# receiver_rfm95.net
KiCad netlist of a schematic drawn in EAGLE
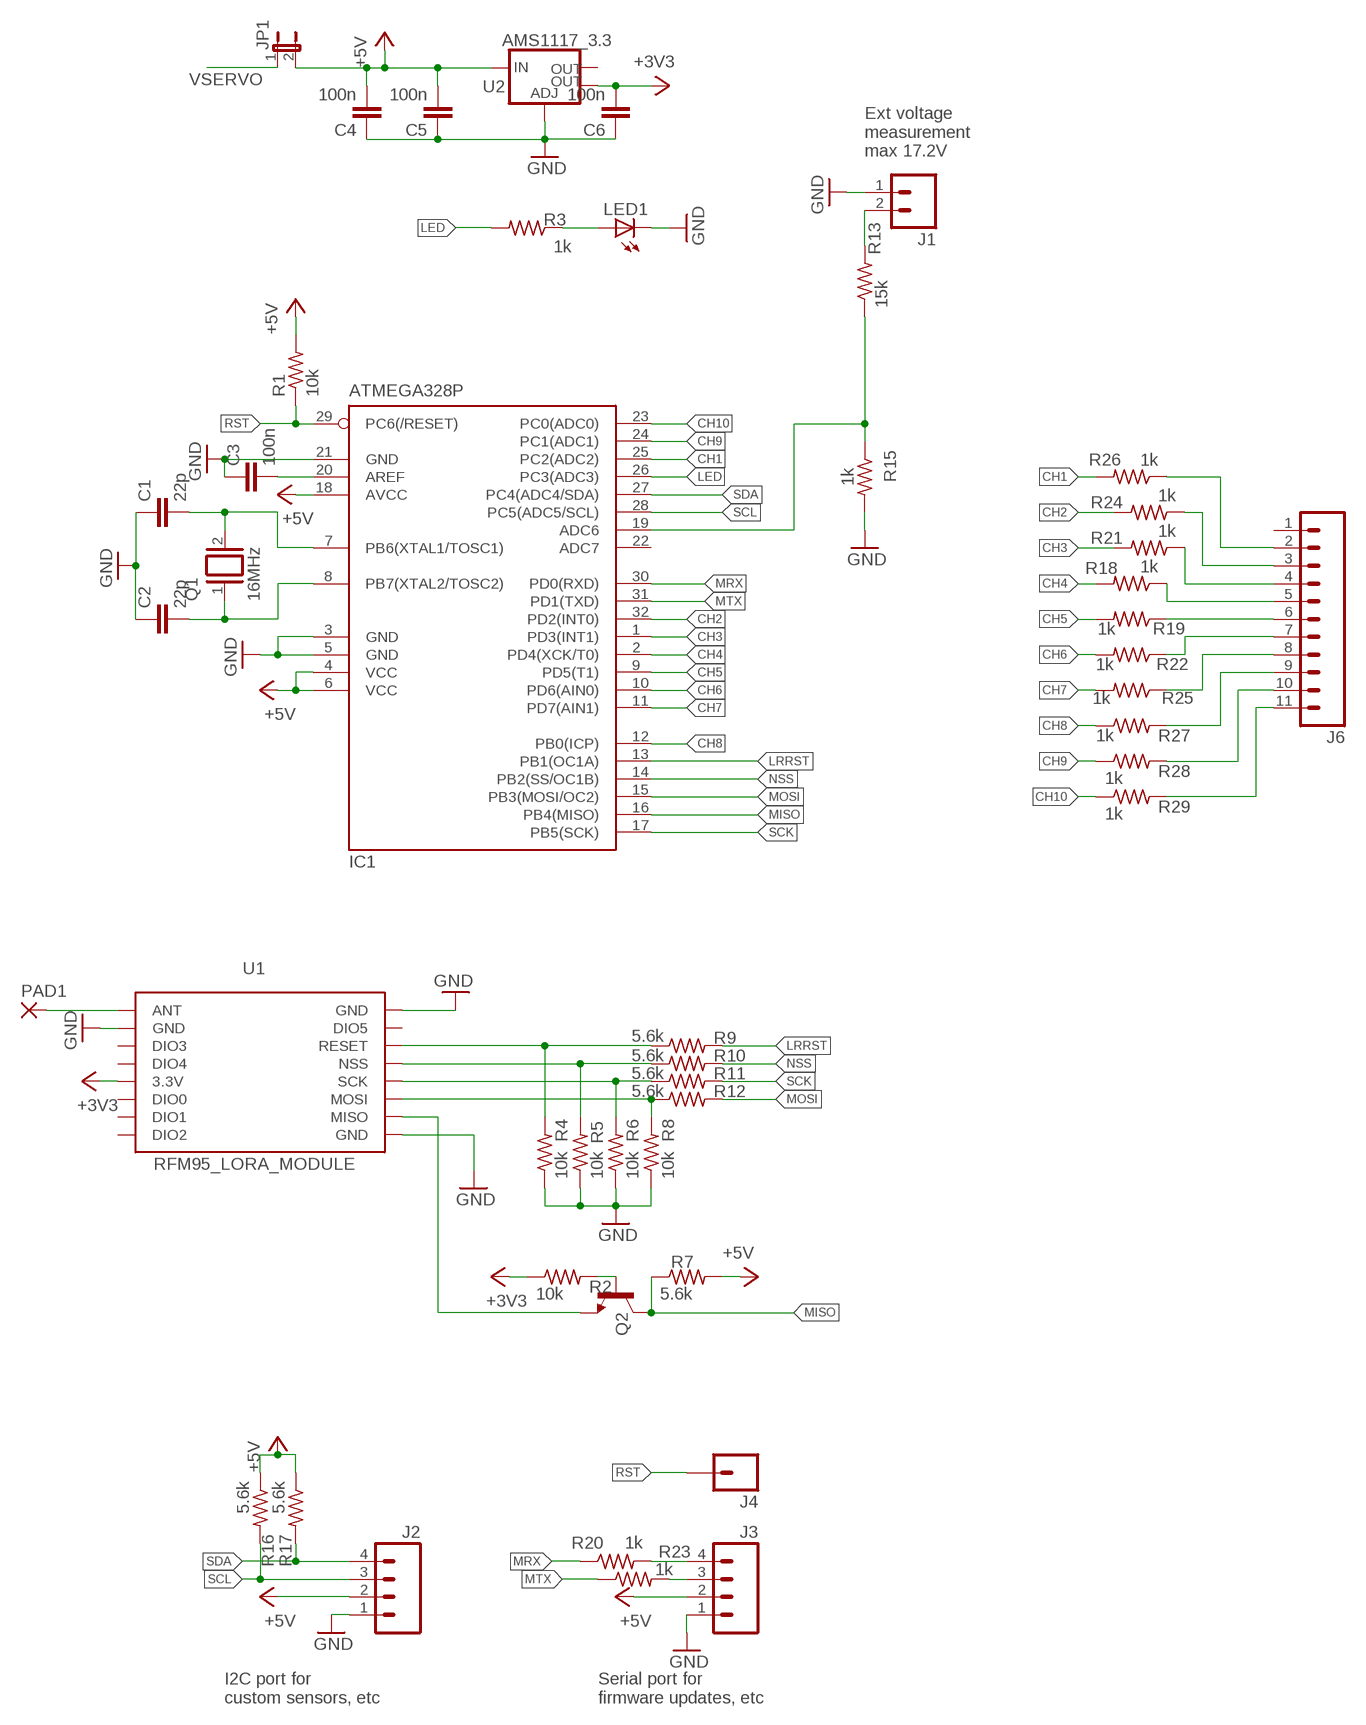
[diagram p0: schematic, sheet 1]

(export (version "E")
  (design (tool "Eeschema 10.0.6"))
  (components
    (comp (ref "C1")
      (value "22p")
      (footprint "eagle-import:C0805K")
      (libsource (lib "eagle-import") (part "C-EUC0805K"))
    )
    (comp (ref "C2")
      (value "22p")
      (footprint "eagle-import:C0805K")
      (libsource (lib "eagle-import") (part "C-EUC0805K"))
    )
    (comp (ref "C3")
      (value "100n")
      (footprint "eagle-import:C0805K")
      (libsource (lib "eagle-import") (part "C-EUC0805K"))
    )
    (comp (ref "C4")
      (value "100n")
      (footprint "eagle-import:C0805K")
      (libsource (lib "eagle-import") (part "C-EUC0805K"))
    )
    (comp (ref "C5")
      (value "100n")
      (footprint "eagle-import:C0805K")
      (libsource (lib "eagle-import") (part "C-EUC0805K"))
    )
    (comp (ref "C6")
      (value "100n")
      (footprint "eagle-import:C0805K")
      (libsource (lib "eagle-import") (part "C-EUC0805K"))
    )
    (comp (ref "IC1")
      (value "ATMEGA328P")
      (footprint "eagle-import:TQFP32-08")
      (fields (field (name "MPN") "ATMEGA8-16AU"))
      (libsource (lib "eagle-import") (part "MEGA8-AI"))
    )
    (comp (ref "J1")
      (value "M02PTH")
      (footprint "eagle-import:1X02")
      (libsource (lib "eagle-import") (part "M02PTH"))
    )
    (comp (ref "J2")
      (value "M04PTH")
      (footprint "eagle-import:1X04")
      (libsource (lib "eagle-import") (part "M04PTH"))
    )
    (comp (ref "J3")
      (value "M04PTH")
      (footprint "eagle-import:1X04")
      (libsource (lib "eagle-import") (part "M04PTH"))
    )
    (comp (ref "J4")
      (value "M01PTH")
      (footprint "eagle-import:1X01")
      (libsource (lib "eagle-import") (part "M01PTH"))
    )
    (comp (ref "J6")
      (value "M11PTH")
      (footprint "eagle-import:1X11")
      (libsource (lib "eagle-import") (part "M11PTH"))
    )
    (comp (ref "JP1")
      (value "JP1E")
      (footprint "eagle-import:JP1")
      (libsource (lib "eagle-import") (part "JP1E"))
    )
    (comp (ref "LED1")
      (value "LEDCHIPLED_1206")
      (footprint "eagle-import:CHIPLED_1206")
      (libsource (lib "eagle-import") (part "LEDCHIPLED_1206"))
    )
    (comp (ref "PAD1")
      (value "2,15/1,0")
      (footprint "eagle-import:2,15_1,0")
      (libsource (lib "eagle-import") (part "2,15/1,0"))
    )
    (comp (ref "Q1")
      (value "16MHz")
      (footprint "eagle-import:QS")
      (libsource (lib "eagle-import") (part "XTAL/S"))
    )
    (comp (ref "Q2")
      (value "BC817-16SMD")
      (footprint "eagle-import:SOT23-BEC")
      (libsource (lib "eagle-import") (part "BC817SMD-16"))
    )
    (comp (ref "R1")
      (value "10k")
      (footprint "eagle-import:R0805")
      (libsource (lib "eagle-import") (part "R-US_R0805"))
    )
    (comp (ref "R2")
      (value "10k")
      (footprint "eagle-import:R0805")
      (libsource (lib "eagle-import") (part "R-US_R0805"))
    )
    (comp (ref "R3")
      (value "1k")
      (footprint "eagle-import:R0805")
      (libsource (lib "eagle-import") (part "R-US_R0805"))
    )
    (comp (ref "R4")
      (value "10k")
      (footprint "eagle-import:R0805")
      (libsource (lib "eagle-import") (part "R-US_R0805"))
    )
    (comp (ref "R5")
      (value "10k")
      (footprint "eagle-import:R0805")
      (libsource (lib "eagle-import") (part "R-US_R0805"))
    )
    (comp (ref "R6")
      (value "10k")
      (footprint "eagle-import:R0805")
      (libsource (lib "eagle-import") (part "R-US_R0805"))
    )
    (comp (ref "R7")
      (value "5.6k")
      (footprint "eagle-import:R0805")
      (libsource (lib "eagle-import") (part "R-US_R0805"))
    )
    (comp (ref "R8")
      (value "10k")
      (footprint "eagle-import:R0805")
      (libsource (lib "eagle-import") (part "R-US_R0805"))
    )
    (comp (ref "R9")
      (value "5.6k")
      (footprint "eagle-import:R0805")
      (libsource (lib "eagle-import") (part "R-US_R0805"))
    )
    (comp (ref "R10")
      (value "5.6k")
      (footprint "eagle-import:R0805")
      (libsource (lib "eagle-import") (part "R-US_R0805"))
    )
    (comp (ref "R11")
      (value "5.6k")
      (footprint "eagle-import:R0805")
      (libsource (lib "eagle-import") (part "R-US_R0805"))
    )
    (comp (ref "R12")
      (value "5.6k")
      (footprint "eagle-import:R0805")
      (libsource (lib "eagle-import") (part "R-US_R0805"))
    )
    (comp (ref "R13")
      (value "15k")
      (footprint "eagle-import:R0805")
      (libsource (lib "eagle-import") (part "R-US_R0805"))
    )
    (comp (ref "R15")
      (value "1k")
      (footprint "eagle-import:R0805")
      (libsource (lib "eagle-import") (part "R-US_R0805"))
    )
    (comp (ref "R16")
      (value "5.6k")
      (footprint "eagle-import:R0805")
      (libsource (lib "eagle-import") (part "R-US_R0805"))
    )
    (comp (ref "R17")
      (value "5.6k")
      (footprint "eagle-import:R0805")
      (libsource (lib "eagle-import") (part "R-US_R0805"))
    )
    (comp (ref "R18")
      (value "1k")
      (footprint "eagle-import:R0805")
      (libsource (lib "eagle-import") (part "R-US_R0805"))
    )
    (comp (ref "R19")
      (value "1k")
      (footprint "eagle-import:R0805")
      (libsource (lib "eagle-import") (part "R-US_R0805"))
    )
    (comp (ref "R20")
      (value "1k")
      (footprint "eagle-import:R0805")
      (libsource (lib "eagle-import") (part "R-US_R0805"))
    )
    (comp (ref "R21")
      (value "1k")
      (footprint "eagle-import:R0805")
      (libsource (lib "eagle-import") (part "R-US_R0805"))
    )
    (comp (ref "R22")
      (value "1k")
      (footprint "eagle-import:R0805")
      (libsource (lib "eagle-import") (part "R-US_R0805"))
    )
    (comp (ref "R23")
      (value "1k")
      (footprint "eagle-import:R0805")
      (libsource (lib "eagle-import") (part "R-US_R0805"))
    )
    (comp (ref "R24")
      (value "1k")
      (footprint "eagle-import:R0805")
      (libsource (lib "eagle-import") (part "R-US_R0805"))
    )
    (comp (ref "R25")
      (value "1k")
      (footprint "eagle-import:R0805")
      (libsource (lib "eagle-import") (part "R-US_R0805"))
    )
    (comp (ref "R26")
      (value "1k")
      (footprint "eagle-import:R0805")
      (libsource (lib "eagle-import") (part "R-US_R0805"))
    )
    (comp (ref "R27")
      (value "1k")
      (footprint "eagle-import:R0805")
      (libsource (lib "eagle-import") (part "R-US_R0805"))
    )
    (comp (ref "R28")
      (value "1k")
      (footprint "eagle-import:R0805")
      (libsource (lib "eagle-import") (part "R-US_R0805"))
    )
    (comp (ref "R29")
      (value "1k")
      (footprint "eagle-import:R0805")
      (libsource (lib "eagle-import") (part "R-US_R0805"))
    )
    (comp (ref "U1")
      (value "RFM95_LORA_MODULE")
      (footprint "eagle-import:RFM95")
      (libsource (lib "eagle-import") (part "RFM95_LORA_MODULE"))
    )
    (comp (ref "U2")
      (value "AMS1117_3.3")
      (footprint "eagle-import:SOT223")
      (libsource (lib "eagle-import") (part "V_REG_LM1117SOT223"))
    )
  )
  (nets
    (net (code "1") (name "+3V3") (class "Default")
      (node (ref "C6") (pin "2") (pinfunction "2_2") (pintype "passive"))
      (node (ref "R2") (pin "1") (pinfunction "1_1") (pintype "passive"))
      (node (ref "U1") (pin "3.3V") (pinfunction "3.3V_3.3V") (pintype "bidirectional"))
      (node (ref "U2") (pin "4") (pinfunction "OUT_4") (pintype "output"))
    )
    (net (code "2") (name "+5V") (class "Default")
      (node (ref "C4") (pin "2") (pinfunction "2_2") (pintype "passive"))
      (node (ref "C5") (pin "2") (pinfunction "2_2") (pintype "passive"))
      (node (ref "IC1") (pin "18") (pinfunction "AVCC_18") (pintype "power_in"))
      (node (ref "IC1") (pin "4") (pinfunction "VCC_4") (pintype "power_in"))
      (node (ref "IC1") (pin "6") (pinfunction "VCC_6") (pintype "power_in"))
      (node (ref "J2") (pin "2") (pinfunction "2_2") (pintype "passive"))
      (node (ref "J3") (pin "2") (pinfunction "2_2") (pintype "passive"))
      (node (ref "JP1") (pin "2") (pinfunction "2_2") (pintype "passive"))
      (node (ref "R1") (pin "2") (pinfunction "2_2") (pintype "passive"))
      (node (ref "R16") (pin "1") (pinfunction "1_1") (pintype "passive"))
      (node (ref "R17") (pin "1") (pinfunction "1_1") (pintype "passive"))
      (node (ref "R7") (pin "2") (pinfunction "2_2") (pintype "passive"))
      (node (ref "U2") (pin "3") (pinfunction "IN_3") (pintype "input"))
    )
    (net (code "3") (name "/DIO3") (class "Default")
      (node (ref "U1") (pin "DIO3") (pinfunction "DIO3_DIO3") (pintype "power_in"))
    )
    (net (code "4") (name "/VSERVO") (class "Default")
      (node (ref "JP1") (pin "1") (pinfunction "1_1") (pintype "passive"))
    )
    (net (code "5") (name "CH1") (class "Default")
      (node (ref "IC1") (pin "25") (pinfunction "PC2(ADC2)_25") (pintype "bidirectional"))
      (node (ref "R26") (pin "2") (pinfunction "2_2") (pintype "passive"))
    )
    (net (code "6") (name "CH2") (class "Default")
      (node (ref "IC1") (pin "32") (pinfunction "PD2(INT0)_32") (pintype "bidirectional"))
      (node (ref "R24") (pin "2") (pinfunction "2_2") (pintype "passive"))
    )
    (net (code "7") (name "CH3") (class "Default")
      (node (ref "IC1") (pin "1") (pinfunction "PD3(INT1)_1") (pintype "bidirectional"))
      (node (ref "R21") (pin "2") (pinfunction "2_2") (pintype "passive"))
    )
    (net (code "8") (name "CH4") (class "Default")
      (node (ref "IC1") (pin "2") (pinfunction "PD4(XCK/T0)_2") (pintype "bidirectional"))
      (node (ref "R18") (pin "2") (pinfunction "2_2") (pintype "passive"))
    )
    (net (code "9") (name "CH5") (class "Default")
      (node (ref "IC1") (pin "9") (pinfunction "PD5(T1)_9") (pintype "bidirectional"))
      (node (ref "R19") (pin "2") (pinfunction "2_2") (pintype "passive"))
    )
    (net (code "10") (name "CH6") (class "Default")
      (node (ref "IC1") (pin "10") (pinfunction "PD6(AIN0)_10") (pintype "bidirectional"))
      (node (ref "R22") (pin "2") (pinfunction "2_2") (pintype "passive"))
    )
    (net (code "11") (name "CH7") (class "Default")
      (node (ref "IC1") (pin "11") (pinfunction "PD7(AIN1)_11") (pintype "bidirectional"))
      (node (ref "R25") (pin "2") (pinfunction "2_2") (pintype "passive"))
    )
    (net (code "12") (name "CH8") (class "Default")
      (node (ref "IC1") (pin "12") (pinfunction "PB0(ICP)_12") (pintype "bidirectional"))
      (node (ref "R27") (pin "1") (pinfunction "1_1") (pintype "passive"))
    )
    (net (code "13") (name "CH9") (class "Default")
      (node (ref "IC1") (pin "24") (pinfunction "PC1(ADC1)_24") (pintype "bidirectional"))
      (node (ref "R28") (pin "1") (pinfunction "1_1") (pintype "passive"))
    )
    (net (code "14") (name "CH10") (class "Default")
      (node (ref "IC1") (pin "23") (pinfunction "PC0(ADC0)_23") (pintype "bidirectional"))
      (node (ref "R29") (pin "1") (pinfunction "1_1") (pintype "passive"))
    )
    (net (code "15") (name "GND") (class "Default")
      (node (ref "C1") (pin "1") (pinfunction "1_1") (pintype "passive"))
      (node (ref "C2") (pin "1") (pinfunction "1_1") (pintype "passive"))
      (node (ref "C3") (pin "1") (pinfunction "1_1") (pintype "passive"))
      (node (ref "C4") (pin "1") (pinfunction "1_1") (pintype "passive"))
      (node (ref "C5") (pin "1") (pinfunction "1_1") (pintype "passive"))
      (node (ref "C6") (pin "1") (pinfunction "1_1") (pintype "passive"))
      (node (ref "IC1") (pin "21") (pinfunction "GND_21") (pintype "power_in"))
      (node (ref "IC1") (pin "3") (pinfunction "GND_3") (pintype "power_in"))
      (node (ref "IC1") (pin "5") (pinfunction "GND_5") (pintype "power_in"))
      (node (ref "J1") (pin "1") (pinfunction "1_1") (pintype "passive"))
      (node (ref "J2") (pin "1") (pinfunction "1_1") (pintype "passive"))
      (node (ref "J3") (pin "1") (pinfunction "1_1") (pintype "passive"))
      (node (ref "LED1") (pin "C") (pinfunction "C_C") (pintype "passive"))
      (node (ref "R15") (pin "2") (pinfunction "2_2") (pintype "passive"))
      (node (ref "R4") (pin "1") (pinfunction "1_1") (pintype "passive"))
      (node (ref "R5") (pin "1") (pinfunction "1_1") (pintype "passive"))
      (node (ref "R6") (pin "1") (pinfunction "1_1") (pintype "passive"))
      (node (ref "R8") (pin "1") (pinfunction "1_1") (pintype "passive"))
      (node (ref "U1") (pin "GND") (pinfunction "GND_GND") (pintype "power_in"))
      (node (ref "U1") (pin "GND@1") (pinfunction "GND_GND@1") (pintype "power_in"))
      (node (ref "U1") (pin "GND@2") (pinfunction "GND_GND@2") (pintype "power_in"))
      (node (ref "U2") (pin "1") (pinfunction "ADJ_1") (pintype "input"))
    )
    (net (code "16") (name "LED") (class "Default")
      (node (ref "IC1") (pin "26") (pinfunction "PC3(ADC3)_26") (pintype "bidirectional"))
      (node (ref "R3") (pin "2") (pinfunction "2_2") (pintype "passive"))
    )
    (net (code "17") (name "LRRST") (class "Default")
      (node (ref "IC1") (pin "13") (pinfunction "PB1(OC1A)_13") (pintype "bidirectional"))
      (node (ref "R9") (pin "2") (pinfunction "2_2") (pintype "passive"))
    )
    (net (code "18") (name "MISO") (class "Default")
      (node (ref "IC1") (pin "16") (pinfunction "PB4(MISO)_16") (pintype "bidirectional"))
      (node (ref "Q2") (pin "C") (pinfunction "C_C") (pintype "passive"))
      (node (ref "R7") (pin "1") (pinfunction "1_1") (pintype "passive"))
    )
    (net (code "19") (name "MOSI") (class "Default")
      (node (ref "IC1") (pin "15") (pinfunction "PB3(MOSI/OC2)_15") (pintype "bidirectional"))
      (node (ref "R12") (pin "2") (pinfunction "2_2") (pintype "passive"))
    )
    (net (code "20") (name "MRX") (class "Default")
      (node (ref "IC1") (pin "30") (pinfunction "PD0(RXD)_30") (pintype "bidirectional"))
      (node (ref "R20") (pin "1") (pinfunction "1_1") (pintype "passive"))
    )
    (net (code "21") (name "MTX") (class "Default")
      (node (ref "IC1") (pin "31") (pinfunction "PD1(TXD)_31") (pintype "bidirectional"))
      (node (ref "R23") (pin "1") (pinfunction "1_1") (pintype "passive"))
    )
    (net (code "22") (name "NSS") (class "Default")
      (node (ref "IC1") (pin "14") (pinfunction "PB2(SS/OC1B)_14") (pintype "bidirectional"))
      (node (ref "R10") (pin "2") (pinfunction "2_2") (pintype "passive"))
    )
    (net (code "23") (name "Net-(IC1-ADC6)") (class "Default")
      (node (ref "IC1") (pin "19") (pinfunction "ADC6_19") (pintype "bidirectional"))
      (node (ref "R13") (pin "1") (pinfunction "1_1") (pintype "passive"))
      (node (ref "R15") (pin "1") (pinfunction "1_1") (pintype "passive"))
    )
    (net (code "24") (name "Net-(IC1-AREF)") (class "Default")
      (node (ref "C3") (pin "2") (pinfunction "2_2") (pintype "passive"))
      (node (ref "IC1") (pin "20") (pinfunction "AREF_20") (pintype "passive"))
    )
    (net (code "25") (name "Net-(IC1-PB6(XTAL1{slash}TOSC1))") (class "Default")
      (node (ref "C1") (pin "2") (pinfunction "2_2") (pintype "passive"))
      (node (ref "IC1") (pin "7") (pinfunction "PB6(XTAL1/TOSC1)_7") (pintype "bidirectional"))
      (node (ref "Q1") (pin "2") (pinfunction "2_2") (pintype "passive"))
    )
    (net (code "26") (name "Net-(IC1-PB7(XTAL2{slash}TOSC2))") (class "Default")
      (node (ref "C2") (pin "2") (pinfunction "2_2") (pintype "passive"))
      (node (ref "IC1") (pin "8") (pinfunction "PB7(XTAL2/TOSC2)_8") (pintype "bidirectional"))
      (node (ref "Q1") (pin "1") (pinfunction "1_1") (pintype "passive"))
    )
    (net (code "27") (name "Net-(J1-Pad2)") (class "Default")
      (node (ref "J1") (pin "2") (pinfunction "2_2") (pintype "passive"))
      (node (ref "R13") (pin "2") (pinfunction "2_2") (pintype "passive"))
    )
    (net (code "28") (name "Net-(J3-Pad3)") (class "Default")
      (node (ref "J3") (pin "3") (pinfunction "3_3") (pintype "passive"))
      (node (ref "R23") (pin "2") (pinfunction "2_2") (pintype "passive"))
    )
    (net (code "29") (name "Net-(J3-Pad4)") (class "Default")
      (node (ref "J3") (pin "4") (pinfunction "4_4") (pintype "passive"))
      (node (ref "R20") (pin "2") (pinfunction "2_2") (pintype "passive"))
    )
    (net (code "30") (name "Net-(J6-Pad2)") (class "Default")
      (node (ref "J6") (pin "2") (pinfunction "2_2") (pintype "passive"))
      (node (ref "R26") (pin "1") (pinfunction "1_1") (pintype "passive"))
    )
    (net (code "31") (name "Net-(J6-Pad3)") (class "Default")
      (node (ref "J6") (pin "3") (pinfunction "3_3") (pintype "passive"))
      (node (ref "R24") (pin "1") (pinfunction "1_1") (pintype "passive"))
    )
    (net (code "32") (name "Net-(J6-Pad4)") (class "Default")
      (node (ref "J6") (pin "4") (pinfunction "4_4") (pintype "passive"))
      (node (ref "R21") (pin "1") (pinfunction "1_1") (pintype "passive"))
    )
    (net (code "33") (name "Net-(J6-Pad5)") (class "Default")
      (node (ref "J6") (pin "5") (pinfunction "5_5") (pintype "passive"))
      (node (ref "R18") (pin "1") (pinfunction "1_1") (pintype "passive"))
    )
    (net (code "34") (name "Net-(J6-Pad6)") (class "Default")
      (node (ref "J6") (pin "6") (pinfunction "6_6") (pintype "passive"))
      (node (ref "R19") (pin "1") (pinfunction "1_1") (pintype "passive"))
    )
    (net (code "35") (name "Net-(J6-Pad7)") (class "Default")
      (node (ref "J6") (pin "7") (pinfunction "7_7") (pintype "passive"))
      (node (ref "R22") (pin "1") (pinfunction "1_1") (pintype "passive"))
    )
    (net (code "36") (name "Net-(J6-Pad8)") (class "Default")
      (node (ref "J6") (pin "8") (pinfunction "8_8") (pintype "passive"))
      (node (ref "R25") (pin "1") (pinfunction "1_1") (pintype "passive"))
    )
    (net (code "37") (name "Net-(J6-Pad9)") (class "Default")
      (node (ref "J6") (pin "9") (pinfunction "9_9") (pintype "passive"))
      (node (ref "R27") (pin "2") (pinfunction "2_2") (pintype "passive"))
    )
    (net (code "38") (name "Net-(J6-Pad10)") (class "Default")
      (node (ref "J6") (pin "10") (pinfunction "10_10") (pintype "passive"))
      (node (ref "R28") (pin "2") (pinfunction "2_2") (pintype "passive"))
    )
    (net (code "39") (name "Net-(J6-Pad11)") (class "Default")
      (node (ref "J6") (pin "11") (pinfunction "11_11") (pintype "passive"))
      (node (ref "R29") (pin "2") (pinfunction "2_2") (pintype "passive"))
    )
    (net (code "40") (name "Net-(LED1-PadA)") (class "Default")
      (node (ref "LED1") (pin "A") (pinfunction "A_A") (pintype "passive"))
      (node (ref "R3") (pin "1") (pinfunction "1_1") (pintype "passive"))
    )
    (net (code "41") (name "Net-(PAD1-P)") (class "Default")
      (node (ref "PAD1") (pin "1") (pinfunction "P_1") (pintype "passive"))
      (node (ref "U1") (pin "ANT") (pinfunction "ANT_ANT") (pintype "power_in"))
    )
    (net (code "42") (name "Net-(Q2-PadB)") (class "Default")
      (node (ref "Q2") (pin "B") (pinfunction "B_B") (pintype "passive"))
      (node (ref "R2") (pin "2") (pinfunction "2_2") (pintype "passive"))
    )
    (net (code "43") (name "Net-(Q2-PadE)") (class "Default")
      (node (ref "Q2") (pin "E") (pinfunction "E_E") (pintype "passive"))
      (node (ref "U1") (pin "MISO") (pinfunction "MISO_MISO") (pintype "bidirectional"))
    )
    (net (code "44") (name "Net-(R4-Pad2)") (class "Default")
      (node (ref "R4") (pin "2") (pinfunction "2_2") (pintype "passive"))
      (node (ref "R9") (pin "1") (pinfunction "1_1") (pintype "passive"))
      (node (ref "U1") (pin "RESET") (pinfunction "RESET_RESET") (pintype "bidirectional"))
    )
    (net (code "45") (name "Net-(R10-Pad1)") (class "Default")
      (node (ref "R10") (pin "1") (pinfunction "1_1") (pintype "passive"))
      (node (ref "R5") (pin "2") (pinfunction "2_2") (pintype "passive"))
      (node (ref "U1") (pin "NSS") (pinfunction "NSS_NSS") (pintype "bidirectional"))
    )
    (net (code "46") (name "Net-(R11-Pad1)") (class "Default")
      (node (ref "R11") (pin "1") (pinfunction "1_1") (pintype "passive"))
      (node (ref "R6") (pin "2") (pinfunction "2_2") (pintype "passive"))
      (node (ref "U1") (pin "SCK") (pinfunction "SCK_SCK") (pintype "bidirectional"))
    )
    (net (code "47") (name "Net-(R12-Pad1)") (class "Default")
      (node (ref "R12") (pin "1") (pinfunction "1_1") (pintype "passive"))
      (node (ref "R8") (pin "2") (pinfunction "2_2") (pintype "passive"))
      (node (ref "U1") (pin "MOSI") (pinfunction "MOSI_MOSI") (pintype "bidirectional"))
    )
    (net (code "48") (name "RST") (class "Default")
      (node (ref "IC1") (pin "29") (pinfunction "PC6(/RESET)_29") (pintype "bidirectional"))
      (node (ref "J4") (pin "1") (pinfunction "1_1") (pintype "passive"))
      (node (ref "R1") (pin "1") (pinfunction "1_1") (pintype "passive"))
    )
    (net (code "49") (name "SCK") (class "Default")
      (node (ref "IC1") (pin "17") (pinfunction "PB5(SCK)_17") (pintype "bidirectional"))
      (node (ref "R11") (pin "2") (pinfunction "2_2") (pintype "passive"))
    )
    (net (code "50") (name "SCL") (class "Default")
      (node (ref "IC1") (pin "28") (pinfunction "PC5(ADC5/SCL)_28") (pintype "bidirectional"))
      (node (ref "J2") (pin "3") (pinfunction "3_3") (pintype "passive"))
      (node (ref "R16") (pin "2") (pinfunction "2_2") (pintype "passive"))
    )
    (net (code "51") (name "SDA") (class "Default")
      (node (ref "IC1") (pin "27") (pinfunction "PC4(ADC4/SDA)_27") (pintype "bidirectional"))
      (node (ref "J2") (pin "4") (pinfunction "4_4") (pintype "passive"))
      (node (ref "R17") (pin "2") (pinfunction "2_2") (pintype "passive"))
    )
    (net (code "52") (name "unconnected-(IC1-ADC7-Pad22)") (class "Default")
      (node (ref "IC1") (pin "22") (pinfunction "ADC7_22") (pintype "bidirectional"))
    )
    (net (code "53") (name "unconnected-(J6-Pad1)") (class "Default")
      (node (ref "J6") (pin "1") (pinfunction "1_1") (pintype "passive"))
    )
    (net (code "54") (name "unconnected-(U1-PadDIO0)") (class "Default")
      (node (ref "U1") (pin "DIO0") (pinfunction "DIO0_DIO0") (pintype "bidirectional"))
    )
    (net (code "55") (name "unconnected-(U1-PadDIO1)") (class "Default")
      (node (ref "U1") (pin "DIO1") (pinfunction "DIO1_DIO1") (pintype "bidirectional"))
    )
    (net (code "56") (name "unconnected-(U1-PadDIO2)") (class "Default")
      (node (ref "U1") (pin "DIO2") (pinfunction "DIO2_DIO2") (pintype "bidirectional"))
    )
    (net (code "57") (name "unconnected-(U1-PadDIO4)") (class "Default")
      (node (ref "U1") (pin "DIO4") (pinfunction "DIO4_DIO4") (pintype "bidirectional"))
    )
    (net (code "58") (name "unconnected-(U1-PadDIO5)") (class "Default")
      (node (ref "U1") (pin "DIO5") (pinfunction "DIO5_DIO5") (pintype "bidirectional"))
    )
    (net (code "59") (name "unconnected-(U2-OUT-Pad2)") (class "Default")
      (node (ref "U2") (pin "2") (pinfunction "OUT_2") (pintype "output"))
    )
  )
)
